# 04-_--.net
KiCad netlist of a schematic drawn in Altium Designer
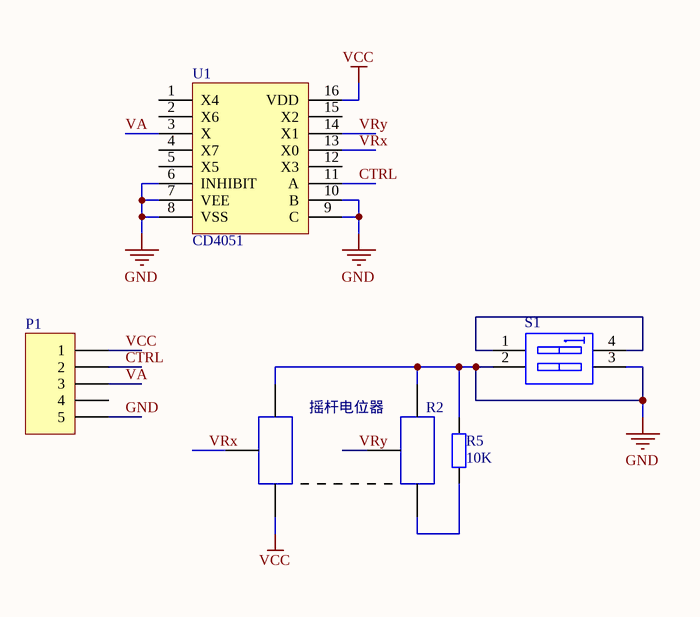
[diagram p0: 04-摇杆模块--原理图.SchDoc]

(export (version "E")
  (design (tool "Eeschema 10.0.6"))
  (components
    (comp (ref "P1")
      (value "Header 5")
      (footprint "USB/SM0.8-6H5")
      (description "Header, 5-Pin")
      (fields (field (name "PUBLISHER") "Altium Limited"))
      (libsource (lib "Miscellaneous Connectors") (part "Header 5"))
    )
    (comp (ref "R2") (value "摇杆电位器") (footprint "摇杆电位器") (libsource (lib "原理图库") (part "电位器")))
    (comp (ref "R5")
      (value "10K")
      (footprint "0805")
      (description "Resistor")
      (fields (field (name "Comment") "Res2") (field (name "PUBLISHER") "Altium Limited"))
      (libsource (lib "Miscellaneous Devices") (part "Res2"))
    )
    (comp (ref "S1")
      (value "SW DIP-2")
      (footprint "Button")
      (description "DIP Switch, 2 Position, SPST")
      (fields (field (name "PUBLISHER") "Altium Limited"))
      (libsource (lib "Miscellaneous Devices") (part "SW DIP-2"))
    )
    (comp (ref "U1") (value "CD4051") (footprint "SUPER16") (libsource (lib "CD4051") (part "CD4051")))
  )
  (nets
    (net (code "1") (name "/CTRL") (class "Default")
      (node (ref "P1") (pin "2") (pinfunction "2_2") (pintype "passive"))
      (node (ref "U1") (pin "11") (pinfunction "A_11") (pintype "passive"))
    )
    (net (code "2") (name "/VA") (class "Default")
      (node (ref "P1") (pin "3") (pinfunction "3_3") (pintype "passive"))
      (node (ref "U1") (pin "3") (pinfunction "X_3") (pintype "passive"))
    )
    (net (code "3") (name "/VRx") (class "Default")
      (node (ref "R2") (pin "2") (pinfunction "2_2") (pintype "passive"))
      (node (ref "U1") (pin "13") (pinfunction "X0_13") (pintype "passive"))
    )
    (net (code "4") (name "/VRy") (class "Default")
      (node (ref "R2") (pin "5") (pinfunction "5_5") (pintype "passive"))
      (node (ref "U1") (pin "14") (pinfunction "X1_14") (pintype "passive"))
    )
    (net (code "5") (name "GND") (class "Default")
      (node (ref "P1") (pin "5") (pinfunction "5_5") (pintype "passive"))
      (node (ref "R2") (pin "1") (pinfunction "1_1") (pintype "passive"))
      (node (ref "R2") (pin "4") (pinfunction "4_4") (pintype "passive"))
      (node (ref "R5") (pin "2") (pinfunction "2_2") (pintype "passive"))
      (node (ref "S1") (pin "2") (pinfunction "A2_2") (pintype "passive"))
      (node (ref "S1") (pin "3") (pinfunction "B2_3") (pintype "passive"))
      (node (ref "U1") (pin "10") (pinfunction "B_10") (pintype "passive"))
      (node (ref "U1") (pin "6") (pinfunction "INHIBIT_6") (pintype "passive"))
      (node (ref "U1") (pin "7") (pinfunction "VEE_7") (pintype "passive"))
      (node (ref "U1") (pin "8") (pinfunction "VSS_8") (pintype "passive"))
      (node (ref "U1") (pin "9") (pinfunction "C_9") (pintype "passive"))
    )
    (net (code "6") (name "Net-(R2-Pad6)") (class "Default")
      (node (ref "R2") (pin "6") (pinfunction "6_6") (pintype "passive"))
      (node (ref "R5") (pin "1") (pinfunction "1_1") (pintype "passive"))
    )
    (net (code "7") (name "Net-(S1-A1)") (class "Default")
      (node (ref "S1") (pin "1") (pinfunction "A1_1") (pintype "passive"))
      (node (ref "S1") (pin "4") (pinfunction "B1_4") (pintype "passive"))
    )
    (net (code "8") (name "VCC") (class "Default")
      (node (ref "P1") (pin "1") (pinfunction "1_1") (pintype "passive"))
      (node (ref "R2") (pin "3") (pinfunction "3_3") (pintype "passive"))
      (node (ref "U1") (pin "16") (pinfunction "VDD_16") (pintype "passive"))
    )
    (net (code "9") (name "unconnected-(P1-Pad4)") (class "Default")
      (node (ref "P1") (pin "4") (pinfunction "4_4") (pintype "passive"))
    )
    (net (code "10") (name "unconnected-(R2-Pad0)") (class "Default")
      (node (ref "R2") (pin "0") (pinfunction "0_0") (pintype "passive"))
    )
    (net (code "11") (name "unconnected-(U1-X2-Pad15)") (class "Default")
      (node (ref "U1") (pin "15") (pinfunction "X2_15") (pintype "passive"))
    )
    (net (code "12") (name "unconnected-(U1-X3-Pad12)") (class "Default")
      (node (ref "U1") (pin "12") (pinfunction "X3_12") (pintype "passive"))
    )
    (net (code "13") (name "unconnected-(U1-X4-Pad1)") (class "Default")
      (node (ref "U1") (pin "1") (pinfunction "X4_1") (pintype "passive"))
    )
    (net (code "14") (name "unconnected-(U1-X5-Pad5)") (class "Default")
      (node (ref "U1") (pin "5") (pinfunction "X5_5") (pintype "passive"))
    )
    (net (code "15") (name "unconnected-(U1-X6-Pad2)") (class "Default")
      (node (ref "U1") (pin "2") (pinfunction "X6_2") (pintype "passive"))
    )
    (net (code "16") (name "unconnected-(U1-X7-Pad4)") (class "Default")
      (node (ref "U1") (pin "4") (pinfunction "X7_4") (pintype "passive"))
    )
  )
)
